# Sheet5.net
KiCad netlist of a schematic drawn in Altium Designer
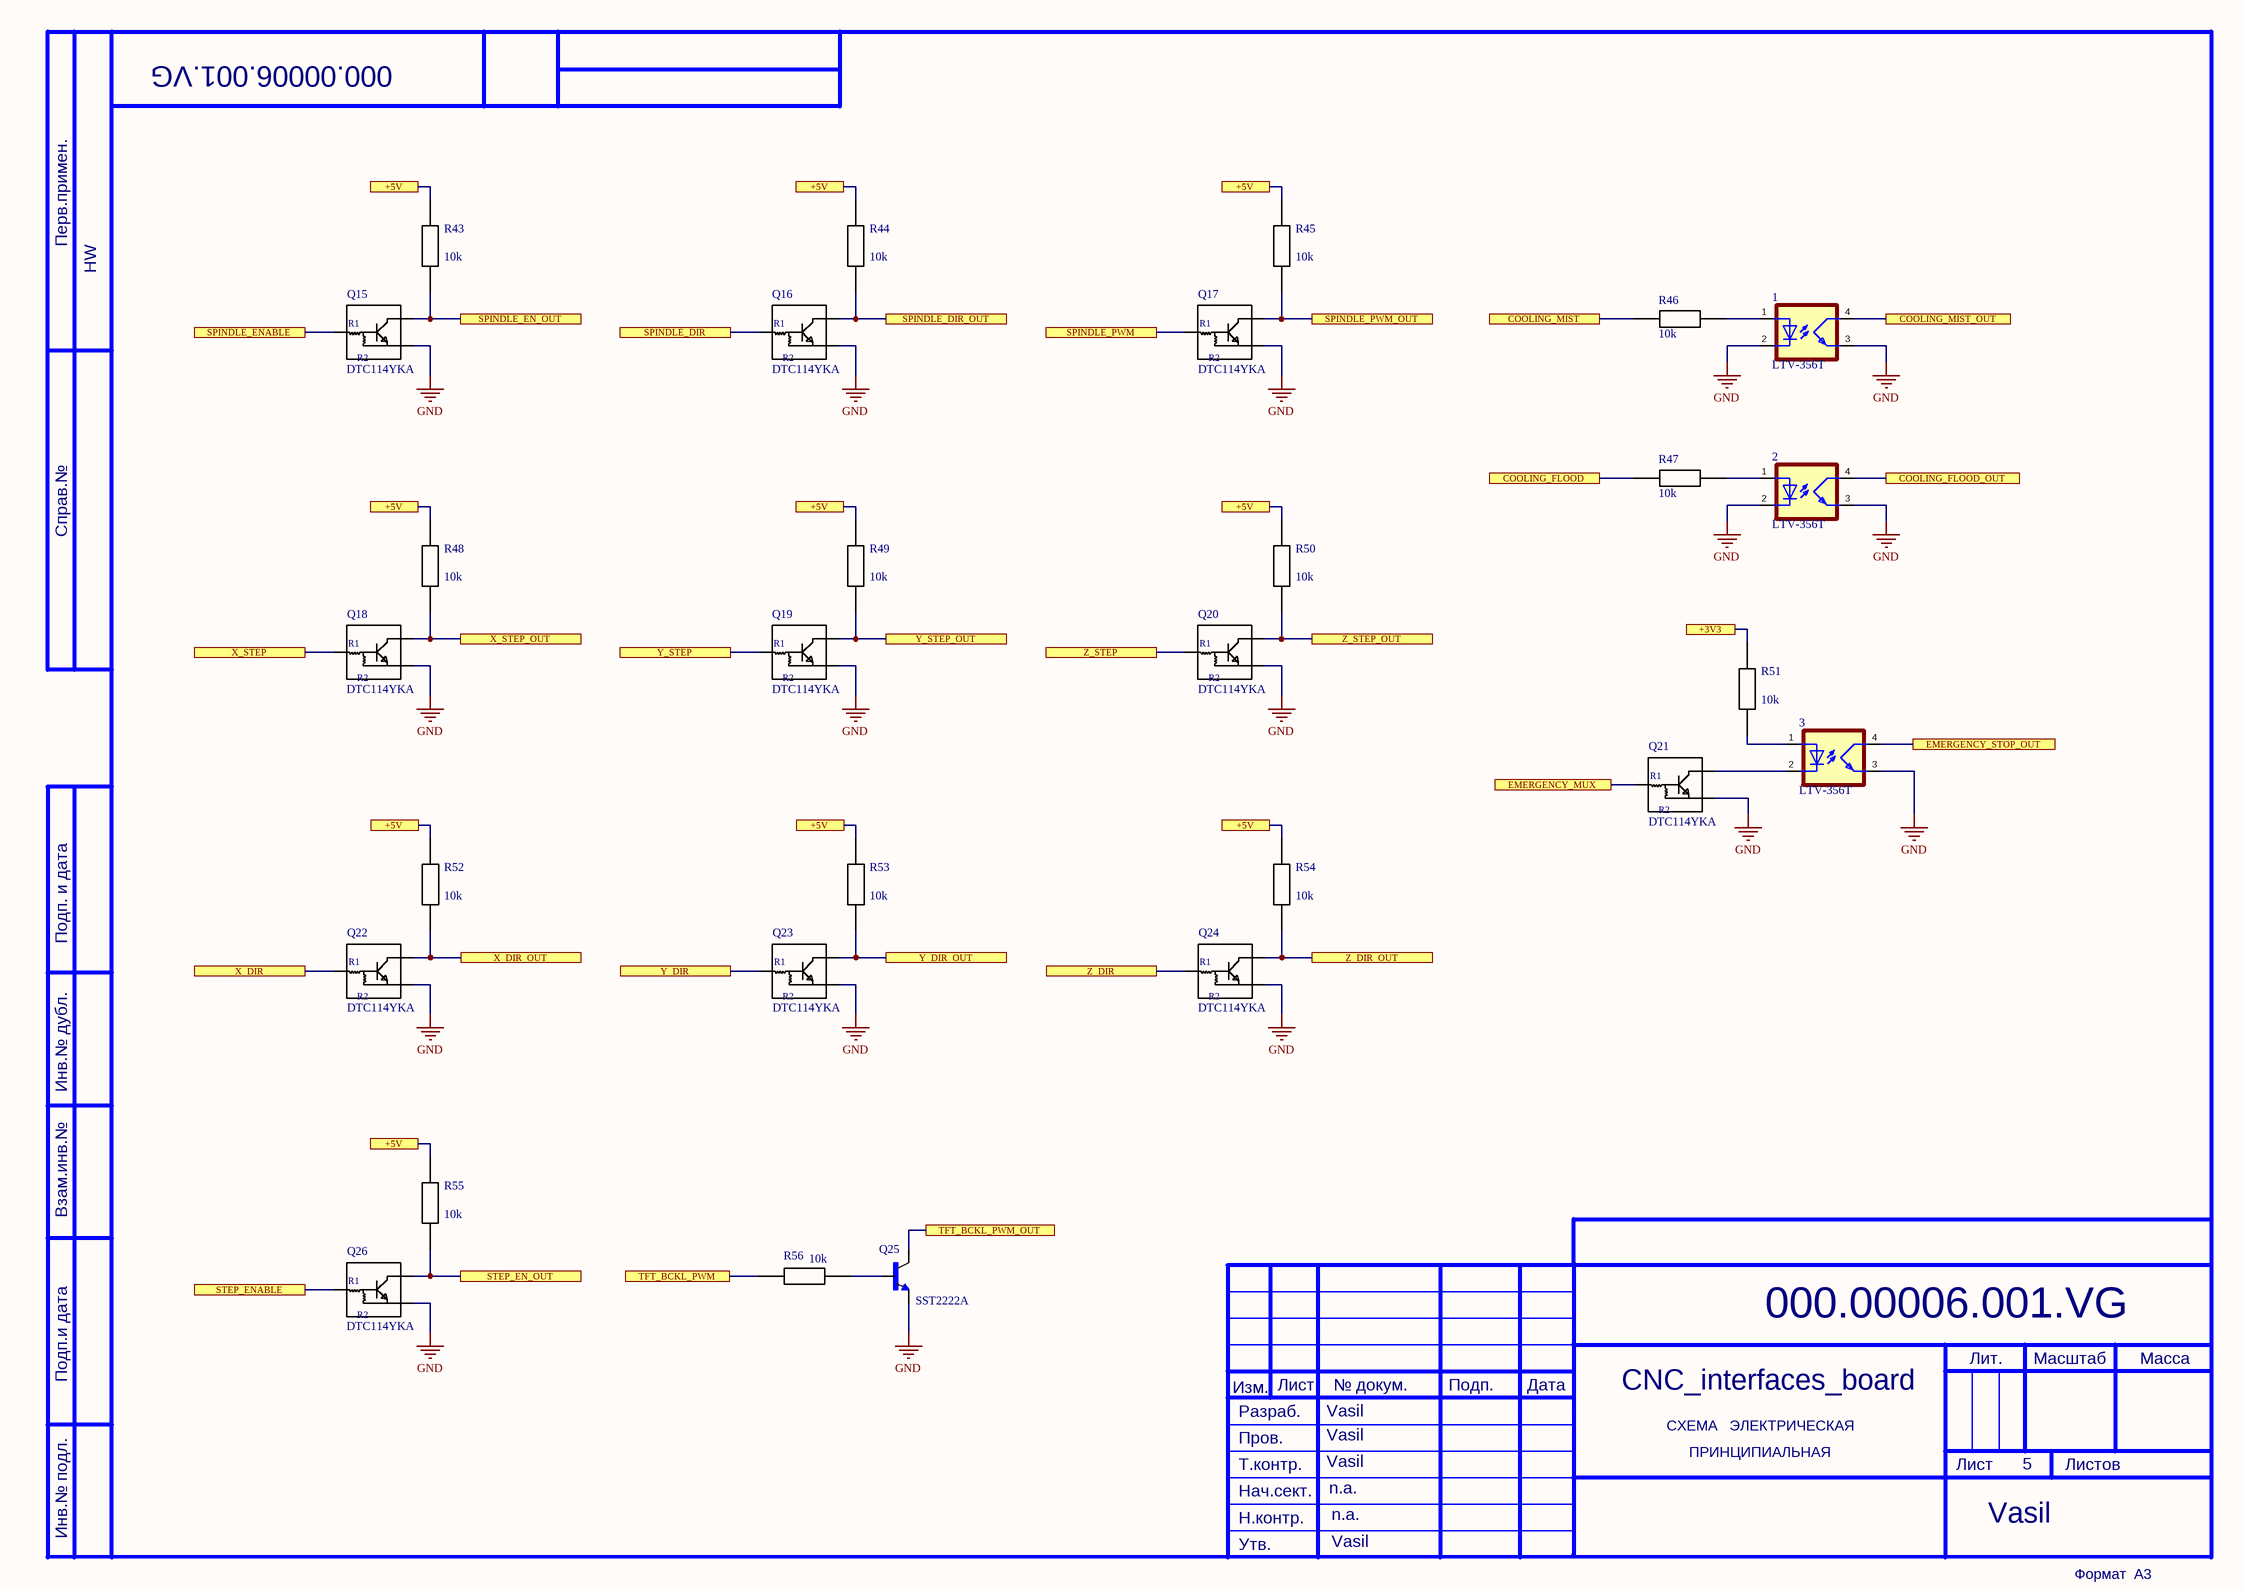
[diagram p0: Sheet5.SchDoc]

(export (version "E")
  (design (tool "Eeschema 10.0.6"))
  (components
    (comp (ref "1")
      (value "LTV-356T")
      (footprint "MINI-FLAT-4")
      (description "Optoisolator Transistor Output 3750Vrms 1 Channel 4-SOP")
      (fields (field (name "MF") "Lite-On Inc."))
      (libsource (lib "CAN_Library") (part "LTV-356T"))
    )
    (comp (ref "2")
      (value "LTV-356T")
      (footprint "MINI-FLAT-4")
      (description "Optoisolator Transistor Output 3750Vrms 1 Channel 4-SOP")
      (fields (field (name "MF") "Lite-On Inc."))
      (libsource (lib "CAN_Library") (part "LTV-356T"))
    )
    (comp (ref "3")
      (value "LTV-356T")
      (footprint "MINI-FLAT-4")
      (description "Optoisolator Transistor Output 3750Vrms 1 Channel 4-SOP")
      (fields (field (name "MF") "Lite-On Inc."))
      (libsource (lib "CAN_Library") (part "LTV-356T"))
    )
    (comp (ref "Q15")
      (value "DTC114YKA")
      (footprint "SOT-346 (SC59) Black")
      (description "NPN Digital 50V 100mA 200mW  R1=10kOm R2=47kOm")
      (fields (field (name "MANUFACTURER") "ROHM Semiconductor"))
      (libsource (lib "CAN_Library") (part "DTC114YKA"))
    )
    (comp (ref "Q16")
      (value "DTC114YKA")
      (footprint "SOT-346 (SC59) Black")
      (description "NPN Digital 50V 100mA 200mW  R1=10kOm R2=47kOm")
      (fields (field (name "MANUFACTURER") "ROHM Semiconductor"))
      (libsource (lib "CAN_Library") (part "DTC114YKA"))
    )
    (comp (ref "Q17")
      (value "DTC114YKA")
      (footprint "SOT-346 (SC59) Black")
      (description "NPN Digital 50V 100mA 200mW  R1=10kOm R2=47kOm")
      (fields (field (name "MANUFACTURER") "ROHM Semiconductor"))
      (libsource (lib "CAN_Library") (part "DTC114YKA"))
    )
    (comp (ref "Q18")
      (value "DTC114YKA")
      (footprint "SOT-346 (SC59) Black")
      (description "NPN Digital 50V 100mA 200mW  R1=10kOm R2=47kOm")
      (fields (field (name "MANUFACTURER") "ROHM Semiconductor"))
      (libsource (lib "CAN_Library") (part "DTC114YKA"))
    )
    (comp (ref "Q19")
      (value "DTC114YKA")
      (footprint "SOT-346 (SC59) Black")
      (description "NPN Digital 50V 100mA 200mW  R1=10kOm R2=47kOm")
      (fields (field (name "MANUFACTURER") "ROHM Semiconductor"))
      (libsource (lib "CAN_Library") (part "DTC114YKA"))
    )
    (comp (ref "Q20")
      (value "DTC114YKA")
      (footprint "SOT-346 (SC59) Black")
      (description "NPN Digital 50V 100mA 200mW  R1=10kOm R2=47kOm")
      (fields (field (name "MANUFACTURER") "ROHM Semiconductor"))
      (libsource (lib "CAN_Library") (part "DTC114YKA"))
    )
    (comp (ref "Q21")
      (value "DTC114YKA")
      (footprint "SOT-346 (SC59) Black")
      (description "NPN Digital 50V 100mA 200mW  R1=10kOm R2=47kOm")
      (fields (field (name "MANUFACTURER") "ROHM Semiconductor"))
      (libsource (lib "CAN_Library") (part "DTC114YKA"))
    )
    (comp (ref "Q22")
      (value "DTC114YKA")
      (footprint "SOT-346 (SC59) Black")
      (description "NPN Digital 50V 100mA 200mW  R1=10kOm R2=47kOm")
      (fields (field (name "MANUFACTURER") "ROHM Semiconductor"))
      (libsource (lib "CAN_Library") (part "DTC114YKA"))
    )
    (comp (ref "Q23")
      (value "DTC114YKA")
      (footprint "SOT-346 (SC59) Black")
      (description "NPN Digital 50V 100mA 200mW  R1=10kOm R2=47kOm")
      (fields (field (name "MANUFACTURER") "ROHM Semiconductor"))
      (libsource (lib "CAN_Library") (part "DTC114YKA"))
    )
    (comp (ref "Q24")
      (value "DTC114YKA")
      (footprint "SOT-346 (SC59) Black")
      (description "NPN Digital 50V 100mA 200mW  R1=10kOm R2=47kOm")
      (fields (field (name "MANUFACTURER") "ROHM Semiconductor"))
      (libsource (lib "CAN_Library") (part "DTC114YKA"))
    )
    (comp (ref "Q25")
      (value "SST2222A")
      (footprint "SOT-23-3")
      (description "Transistor NPN 40V 600mA 300MHz 350mW")
      (fields (field (name "MANUFACTURER") "ROHM Semiconductor"))
      (libsource (lib "CAN_Library") (part "SST2222A"))
    )
    (comp (ref "Q26")
      (value "DTC114YKA")
      (footprint "SOT-346 (SC59) Black")
      (description "NPN Digital 50V 100mA 200mW  R1=10kOm R2=47kOm")
      (fields (field (name "MANUFACTURER") "ROHM Semiconductor"))
      (libsource (lib "CAN_Library") (part "DTC114YKA"))
    )
    (comp (ref "R43")
      (value "10k")
      (footprint "SMD 0805")
      (description "RES")
      (libsource (lib "CAN_Library") (part "Resistor_1"))
    )
    (comp (ref "R44")
      (value "10k")
      (footprint "SMD 0805")
      (description "RES")
      (libsource (lib "CAN_Library") (part "Resistor_1"))
    )
    (comp (ref "R45")
      (value "10k")
      (footprint "SMD 0805")
      (description "RES")
      (libsource (lib "CAN_Library") (part "Resistor_1"))
    )
    (comp (ref "R46")
      (value "10k")
      (footprint "SMD 0805")
      (description "RES")
      (libsource (lib "CAN_Library") (part "Resistor_1"))
    )
    (comp (ref "R47")
      (value "10k")
      (footprint "SMD 0805")
      (description "RES")
      (libsource (lib "CAN_Library") (part "Resistor_1"))
    )
    (comp (ref "R48")
      (value "10k")
      (footprint "SMD 0805")
      (description "RES")
      (libsource (lib "CAN_Library") (part "Resistor_1"))
    )
    (comp (ref "R49")
      (value "10k")
      (footprint "SMD 0805")
      (description "RES")
      (libsource (lib "CAN_Library") (part "Resistor_1"))
    )
    (comp (ref "R50")
      (value "10k")
      (footprint "SMD 0805")
      (description "RES")
      (libsource (lib "CAN_Library") (part "Resistor_1"))
    )
    (comp (ref "R51")
      (value "10k")
      (footprint "SMD 0805")
      (description "RES")
      (libsource (lib "CAN_Library") (part "Resistor_1"))
    )
    (comp (ref "R52")
      (value "10k")
      (footprint "SMD 0805")
      (description "RES")
      (libsource (lib "CAN_Library") (part "Resistor_1"))
    )
    (comp (ref "R53")
      (value "10k")
      (footprint "SMD 0805")
      (description "RES")
      (libsource (lib "CAN_Library") (part "Resistor_1"))
    )
    (comp (ref "R54")
      (value "10k")
      (footprint "SMD 0805")
      (description "RES")
      (libsource (lib "CAN_Library") (part "Resistor_1"))
    )
    (comp (ref "R55")
      (value "10k")
      (footprint "SMD 0805")
      (description "RES")
      (libsource (lib "CAN_Library") (part "Resistor_1"))
    )
    (comp (ref "R56")
      (value "10k")
      (footprint "SMD 0805")
      (description "RES")
      (libsource (lib "CAN_Library") (part "Resistor_1"))
    )
  )
  (nets
    (net (code "1") (name "/+3V3") (class "Default")
      (node (ref "R51") (pin "1") (pinfunction "1_1") (pintype "passive"))
    )
    (net (code "2") (name "/+5V") (class "Default")
      (node (ref "R43") (pin "1") (pinfunction "1_1") (pintype "passive"))
      (node (ref "R44") (pin "1") (pinfunction "1_1") (pintype "passive"))
      (node (ref "R45") (pin "1") (pinfunction "1_1") (pintype "passive"))
      (node (ref "R48") (pin "1") (pinfunction "1_1") (pintype "passive"))
      (node (ref "R49") (pin "1") (pinfunction "1_1") (pintype "passive"))
      (node (ref "R50") (pin "1") (pinfunction "1_1") (pintype "passive"))
      (node (ref "R52") (pin "1") (pinfunction "1_1") (pintype "passive"))
      (node (ref "R53") (pin "1") (pinfunction "1_1") (pintype "passive"))
      (node (ref "R54") (pin "1") (pinfunction "1_1") (pintype "passive"))
      (node (ref "R55") (pin "1") (pinfunction "1_1") (pintype "passive"))
    )
    (net (code "3") (name "/COOLING_FLOOD") (class "Default")
      (node (ref "R47") (pin "1") (pinfunction "1_1") (pintype "passive"))
    )
    (net (code "4") (name "/COOLING_FLOOD_OUT") (class "Default")
      (node (ref "2") (pin "4") (pinfunction "COL_4") (pintype "passive"))
    )
    (net (code "5") (name "/COOLING_MIST") (class "Default")
      (node (ref "R46") (pin "1") (pinfunction "1_1") (pintype "passive"))
    )
    (net (code "6") (name "/COOLING_MIST_OUT") (class "Default")
      (node (ref "1") (pin "4") (pinfunction "COL_4") (pintype "passive"))
    )
    (net (code "7") (name "/EMERGENCY_MUX") (class "Default")
      (node (ref "Q21") (pin "1") (pinfunction "1_1") (pintype "passive"))
    )
    (net (code "8") (name "/EMERGENCY_STOP_OUT") (class "Default")
      (node (ref "3") (pin "4") (pinfunction "COL_4") (pintype "passive"))
    )
    (net (code "9") (name "/SPINDLE_DIR") (class "Default")
      (node (ref "Q16") (pin "1") (pinfunction "1_1") (pintype "passive"))
    )
    (net (code "10") (name "/SPINDLE_DIR_OUT") (class "Default")
      (node (ref "Q16") (pin "3") (pinfunction "3_3") (pintype "passive"))
      (node (ref "R44") (pin "2") (pinfunction "2_2") (pintype "passive"))
    )
    (net (code "11") (name "/SPINDLE_ENABLE") (class "Default")
      (node (ref "Q15") (pin "1") (pinfunction "1_1") (pintype "passive"))
    )
    (net (code "12") (name "/SPINDLE_EN_OUT") (class "Default")
      (node (ref "Q15") (pin "3") (pinfunction "3_3") (pintype "passive"))
      (node (ref "R43") (pin "2") (pinfunction "2_2") (pintype "passive"))
    )
    (net (code "13") (name "/SPINDLE_PWM") (class "Default")
      (node (ref "Q17") (pin "1") (pinfunction "1_1") (pintype "passive"))
    )
    (net (code "14") (name "/SPINDLE_PWM_OUT") (class "Default")
      (node (ref "Q17") (pin "3") (pinfunction "3_3") (pintype "passive"))
      (node (ref "R45") (pin "2") (pinfunction "2_2") (pintype "passive"))
    )
    (net (code "15") (name "/STEP_ENABLE") (class "Default")
      (node (ref "Q26") (pin "1") (pinfunction "1_1") (pintype "passive"))
    )
    (net (code "16") (name "/STEP_EN_OUT") (class "Default")
      (node (ref "Q26") (pin "3") (pinfunction "3_3") (pintype "passive"))
      (node (ref "R55") (pin "2") (pinfunction "2_2") (pintype "passive"))
    )
    (net (code "17") (name "/TFT_BCKL_PWM") (class "Default")
      (node (ref "R56") (pin "1") (pinfunction "1_1") (pintype "passive"))
    )
    (net (code "18") (name "/TFT_BCKL_PWM_OUT") (class "Default")
      (node (ref "Q25") (pin "3") (pinfunction "C_3") (pintype "passive"))
    )
    (net (code "19") (name "/X_DIR") (class "Default")
      (node (ref "Q22") (pin "1") (pinfunction "1_1") (pintype "passive"))
    )
    (net (code "20") (name "/X_DIR_OUT") (class "Default")
      (node (ref "Q22") (pin "3") (pinfunction "3_3") (pintype "passive"))
      (node (ref "R52") (pin "2") (pinfunction "2_2") (pintype "passive"))
    )
    (net (code "21") (name "/X_STEP") (class "Default")
      (node (ref "Q18") (pin "1") (pinfunction "1_1") (pintype "passive"))
    )
    (net (code "22") (name "/X_STEP_OUT") (class "Default")
      (node (ref "Q18") (pin "3") (pinfunction "3_3") (pintype "passive"))
      (node (ref "R48") (pin "2") (pinfunction "2_2") (pintype "passive"))
    )
    (net (code "23") (name "/Y_DIR") (class "Default")
      (node (ref "Q23") (pin "1") (pinfunction "1_1") (pintype "passive"))
    )
    (net (code "24") (name "/Y_DIR_OUT") (class "Default")
      (node (ref "Q23") (pin "3") (pinfunction "3_3") (pintype "passive"))
      (node (ref "R53") (pin "2") (pinfunction "2_2") (pintype "passive"))
    )
    (net (code "25") (name "/Y_STEP") (class "Default")
      (node (ref "Q19") (pin "1") (pinfunction "1_1") (pintype "passive"))
    )
    (net (code "26") (name "/Y_STEP_OUT") (class "Default")
      (node (ref "Q19") (pin "3") (pinfunction "3_3") (pintype "passive"))
      (node (ref "R49") (pin "2") (pinfunction "2_2") (pintype "passive"))
    )
    (net (code "27") (name "/Z_DIR") (class "Default")
      (node (ref "Q24") (pin "1") (pinfunction "1_1") (pintype "passive"))
    )
    (net (code "28") (name "/Z_DIR_OUT") (class "Default")
      (node (ref "Q24") (pin "3") (pinfunction "3_3") (pintype "passive"))
      (node (ref "R54") (pin "2") (pinfunction "2_2") (pintype "passive"))
    )
    (net (code "29") (name "/Z_STEP") (class "Default")
      (node (ref "Q20") (pin "1") (pinfunction "1_1") (pintype "passive"))
    )
    (net (code "30") (name "/Z_STEP_OUT") (class "Default")
      (node (ref "Q20") (pin "3") (pinfunction "3_3") (pintype "passive"))
      (node (ref "R50") (pin "2") (pinfunction "2_2") (pintype "passive"))
    )
    (net (code "31") (name "GND") (class "Default")
      (node (ref "1") (pin "2") (pinfunction "C_2") (pintype "passive"))
      (node (ref "1") (pin "3") (pinfunction "EMIT_3") (pintype "passive"))
      (node (ref "2") (pin "2") (pinfunction "C_2") (pintype "passive"))
      (node (ref "2") (pin "3") (pinfunction "EMIT_3") (pintype "passive"))
      (node (ref "3") (pin "3") (pinfunction "EMIT_3") (pintype "passive"))
      (node (ref "Q15") (pin "2") (pinfunction "2_2") (pintype "passive"))
      (node (ref "Q16") (pin "2") (pinfunction "2_2") (pintype "passive"))
      (node (ref "Q17") (pin "2") (pinfunction "2_2") (pintype "passive"))
      (node (ref "Q18") (pin "2") (pinfunction "2_2") (pintype "passive"))
      (node (ref "Q19") (pin "2") (pinfunction "2_2") (pintype "passive"))
      (node (ref "Q20") (pin "2") (pinfunction "2_2") (pintype "passive"))
      (node (ref "Q21") (pin "2") (pinfunction "2_2") (pintype "passive"))
      (node (ref "Q22") (pin "2") (pinfunction "2_2") (pintype "passive"))
      (node (ref "Q23") (pin "2") (pinfunction "2_2") (pintype "passive"))
      (node (ref "Q24") (pin "2") (pinfunction "2_2") (pintype "passive"))
      (node (ref "Q25") (pin "2") (pinfunction "E_2") (pintype "passive"))
      (node (ref "Q26") (pin "2") (pinfunction "2_2") (pintype "passive"))
    )
    (net (code "32") (name "Net-(1-A)") (class "Default")
      (node (ref "1") (pin "1") (pinfunction "A_1") (pintype "passive"))
      (node (ref "R46") (pin "2") (pinfunction "2_2") (pintype "passive"))
    )
    (net (code "33") (name "Net-(2-A)") (class "Default")
      (node (ref "2") (pin "1") (pinfunction "A_1") (pintype "passive"))
      (node (ref "R47") (pin "2") (pinfunction "2_2") (pintype "passive"))
    )
    (net (code "34") (name "Net-(3-A)") (class "Default")
      (node (ref "3") (pin "1") (pinfunction "A_1") (pintype "passive"))
      (node (ref "R51") (pin "2") (pinfunction "2_2") (pintype "passive"))
    )
    (net (code "35") (name "Net-(3-C)") (class "Default")
      (node (ref "3") (pin "2") (pinfunction "C_2") (pintype "passive"))
      (node (ref "Q21") (pin "3") (pinfunction "3_3") (pintype "passive"))
    )
    (net (code "36") (name "Net-(Q25-B)") (class "Default")
      (node (ref "Q25") (pin "1") (pinfunction "B_1") (pintype "passive"))
      (node (ref "R56") (pin "2") (pinfunction "2_2") (pintype "passive"))
    )
  )
)
